# Sheet10.net
KiCad netlist of a schematic drawn in Altium Designer
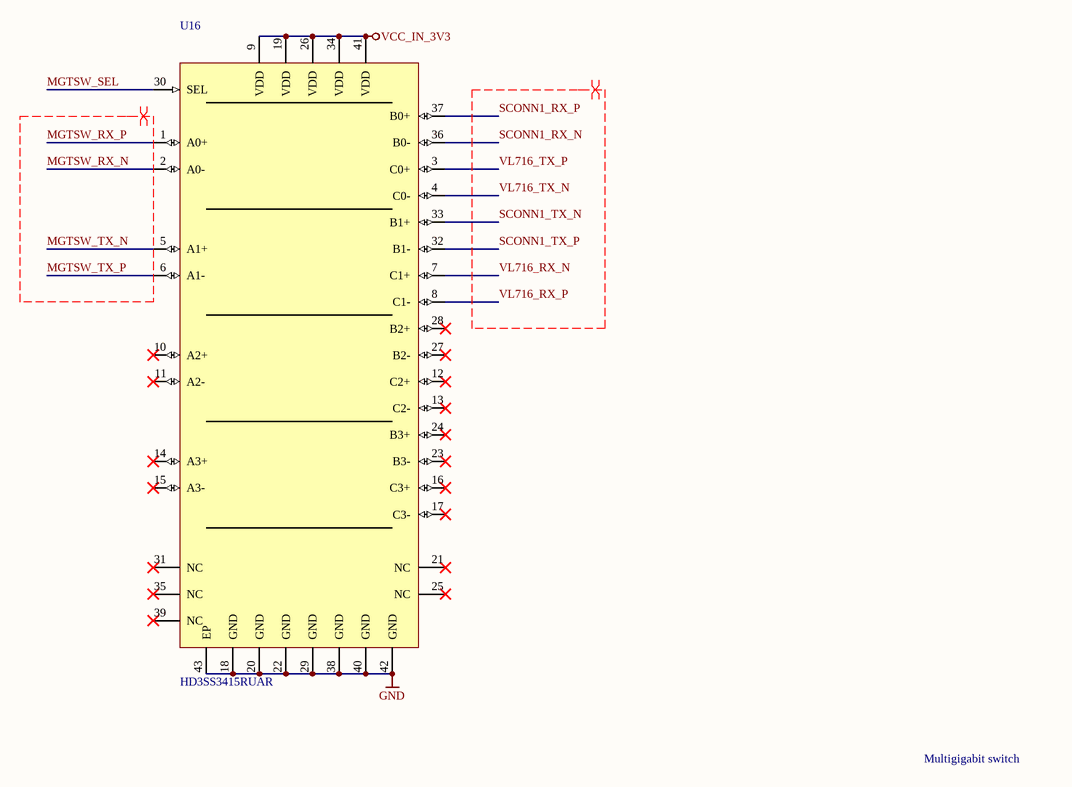
[diagram p0: Sheet10.SchDoc]

(export (version "E")
  (design (tool "Eeschema 10.0.6"))
  (components
    (comp (ref "U16")
      (value "HD3SS3415RUAR")
      (footprint "HD3SS3415RUAR")
      (description "4-Channel High-Performance Differential Switch")
      (libsource (lib "Integrated_Library") (part "HD3SS3415RUAR"))
    )
  )
  (nets
    (net (code "1") (name "/MGTSW_RX_N") (class "Default")
      (node (ref "U16") (pin "2") (pinfunction "A0-_2") (pintype "bidirectional"))
    )
    (net (code "2") (name "/MGTSW_RX_P") (class "Default")
      (node (ref "U16") (pin "1") (pinfunction "A0+_1") (pintype "bidirectional"))
    )
    (net (code "3") (name "/MGTSW_SEL") (class "Default")
      (node (ref "U16") (pin "30") (pinfunction "SEL_30") (pintype "input"))
    )
    (net (code "4") (name "/MGTSW_TX_N") (class "Default")
      (node (ref "U16") (pin "5") (pinfunction "A1+_5") (pintype "bidirectional"))
    )
    (net (code "5") (name "/MGTSW_TX_P") (class "Default")
      (node (ref "U16") (pin "6") (pinfunction "A1-_6") (pintype "bidirectional"))
    )
    (net (code "6") (name "/SCONN1_RX_N") (class "Default")
      (node (ref "U16") (pin "36") (pinfunction "B0-_36") (pintype "bidirectional"))
    )
    (net (code "7") (name "/SCONN1_RX_P") (class "Default")
      (node (ref "U16") (pin "37") (pinfunction "B0+_37") (pintype "bidirectional"))
    )
    (net (code "8") (name "/SCONN1_TX_N") (class "Default")
      (node (ref "U16") (pin "33") (pinfunction "B1+_33") (pintype "bidirectional"))
    )
    (net (code "9") (name "/SCONN1_TX_P") (class "Default")
      (node (ref "U16") (pin "32") (pinfunction "B1-_32") (pintype "bidirectional"))
    )
    (net (code "10") (name "/VL716_RX_N") (class "Default")
      (node (ref "U16") (pin "7") (pinfunction "C1+_7") (pintype "bidirectional"))
    )
    (net (code "11") (name "/VL716_RX_P") (class "Default")
      (node (ref "U16") (pin "8") (pinfunction "C1-_8") (pintype "bidirectional"))
    )
    (net (code "12") (name "/VL716_TX_N") (class "Default")
      (node (ref "U16") (pin "4") (pinfunction "C0-_4") (pintype "bidirectional"))
    )
    (net (code "13") (name "/VL716_TX_P") (class "Default")
      (node (ref "U16") (pin "3") (pinfunction "C0+_3") (pintype "bidirectional"))
    )
    (net (code "14") (name "GND") (class "Default")
      (node (ref "U16") (pin "18") (pinfunction "GND_18") (pintype "power_in"))
      (node (ref "U16") (pin "20") (pinfunction "GND_20") (pintype "power_in"))
      (node (ref "U16") (pin "22") (pinfunction "GND_22") (pintype "power_in"))
      (node (ref "U16") (pin "29") (pinfunction "GND_29") (pintype "power_in"))
      (node (ref "U16") (pin "38") (pinfunction "GND_38") (pintype "power_in"))
      (node (ref "U16") (pin "40") (pinfunction "GND_40") (pintype "power_in"))
      (node (ref "U16") (pin "42") (pinfunction "GND_42") (pintype "power_in"))
      (node (ref "U16") (pin "43") (pinfunction "EP_43") (pintype "power_in"))
    )
    (net (code "15") (name "VCC_IN_3V3") (class "Default")
      (node (ref "U16") (pin "19") (pinfunction "VDD_19") (pintype "power_in"))
      (node (ref "U16") (pin "26") (pinfunction "VDD_26") (pintype "power_in"))
      (node (ref "U16") (pin "34") (pinfunction "VDD_34") (pintype "power_in"))
      (node (ref "U16") (pin "41") (pinfunction "VDD_41") (pintype "power_in"))
      (node (ref "U16") (pin "9") (pinfunction "VDD_9") (pintype "power_in"))
    )
    (net (code "16") (name "unconnected-(U16-A2+-Pad10)") (class "Default")
      (node (ref "U16") (pin "10") (pinfunction "A2+_10") (pintype "bidirectional+no_connect"))
    )
    (net (code "17") (name "unconnected-(U16-A2--Pad11)") (class "Default")
      (node (ref "U16") (pin "11") (pinfunction "A2-_11") (pintype "bidirectional+no_connect"))
    )
    (net (code "18") (name "unconnected-(U16-A3+-Pad14)") (class "Default")
      (node (ref "U16") (pin "14") (pinfunction "A3+_14") (pintype "bidirectional+no_connect"))
    )
    (net (code "19") (name "unconnected-(U16-A3--Pad15)") (class "Default")
      (node (ref "U16") (pin "15") (pinfunction "A3-_15") (pintype "bidirectional+no_connect"))
    )
    (net (code "20") (name "unconnected-(U16-B2+-Pad28)") (class "Default")
      (node (ref "U16") (pin "28") (pinfunction "B2+_28") (pintype "bidirectional+no_connect"))
    )
    (net (code "21") (name "unconnected-(U16-B2--Pad27)") (class "Default")
      (node (ref "U16") (pin "27") (pinfunction "B2-_27") (pintype "bidirectional+no_connect"))
    )
    (net (code "22") (name "unconnected-(U16-B3+-Pad24)") (class "Default")
      (node (ref "U16") (pin "24") (pinfunction "B3+_24") (pintype "bidirectional+no_connect"))
    )
    (net (code "23") (name "unconnected-(U16-B3--Pad23)") (class "Default")
      (node (ref "U16") (pin "23") (pinfunction "B3-_23") (pintype "bidirectional+no_connect"))
    )
    (net (code "24") (name "unconnected-(U16-C2+-Pad12)") (class "Default")
      (node (ref "U16") (pin "12") (pinfunction "C2+_12") (pintype "bidirectional+no_connect"))
    )
    (net (code "25") (name "unconnected-(U16-C2--Pad13)") (class "Default")
      (node (ref "U16") (pin "13") (pinfunction "C2-_13") (pintype "bidirectional+no_connect"))
    )
    (net (code "26") (name "unconnected-(U16-C3+-Pad16)") (class "Default")
      (node (ref "U16") (pin "16") (pinfunction "C3+_16") (pintype "bidirectional+no_connect"))
    )
    (net (code "27") (name "unconnected-(U16-C3--Pad17)") (class "Default")
      (node (ref "U16") (pin "17") (pinfunction "C3-_17") (pintype "bidirectional+no_connect"))
    )
    (net (code "28") (name "unconnected-(U16-NC-Pad21)") (class "Default")
      (node (ref "U16") (pin "21") (pinfunction "NC_21") (pintype "passive+no_connect"))
    )
    (net (code "29") (name "unconnected-(U16-NC-Pad25)") (class "Default")
      (node (ref "U16") (pin "25") (pinfunction "NC_25") (pintype "passive+no_connect"))
    )
    (net (code "30") (name "unconnected-(U16-NC-Pad31)") (class "Default")
      (node (ref "U16") (pin "31") (pinfunction "NC_31") (pintype "passive+no_connect"))
    )
    (net (code "31") (name "unconnected-(U16-NC-Pad35)") (class "Default")
      (node (ref "U16") (pin "35") (pinfunction "NC_35") (pintype "passive+no_connect"))
    )
    (net (code "32") (name "unconnected-(U16-NC-Pad39)") (class "Default")
      (node (ref "U16") (pin "39") (pinfunction "NC_39") (pintype "passive+no_connect"))
    )
  )
)
